# SCH_single_recovery_v1_copy_2022-11-08.net
KiCad netlist of a schematic drawn in EasyEDA
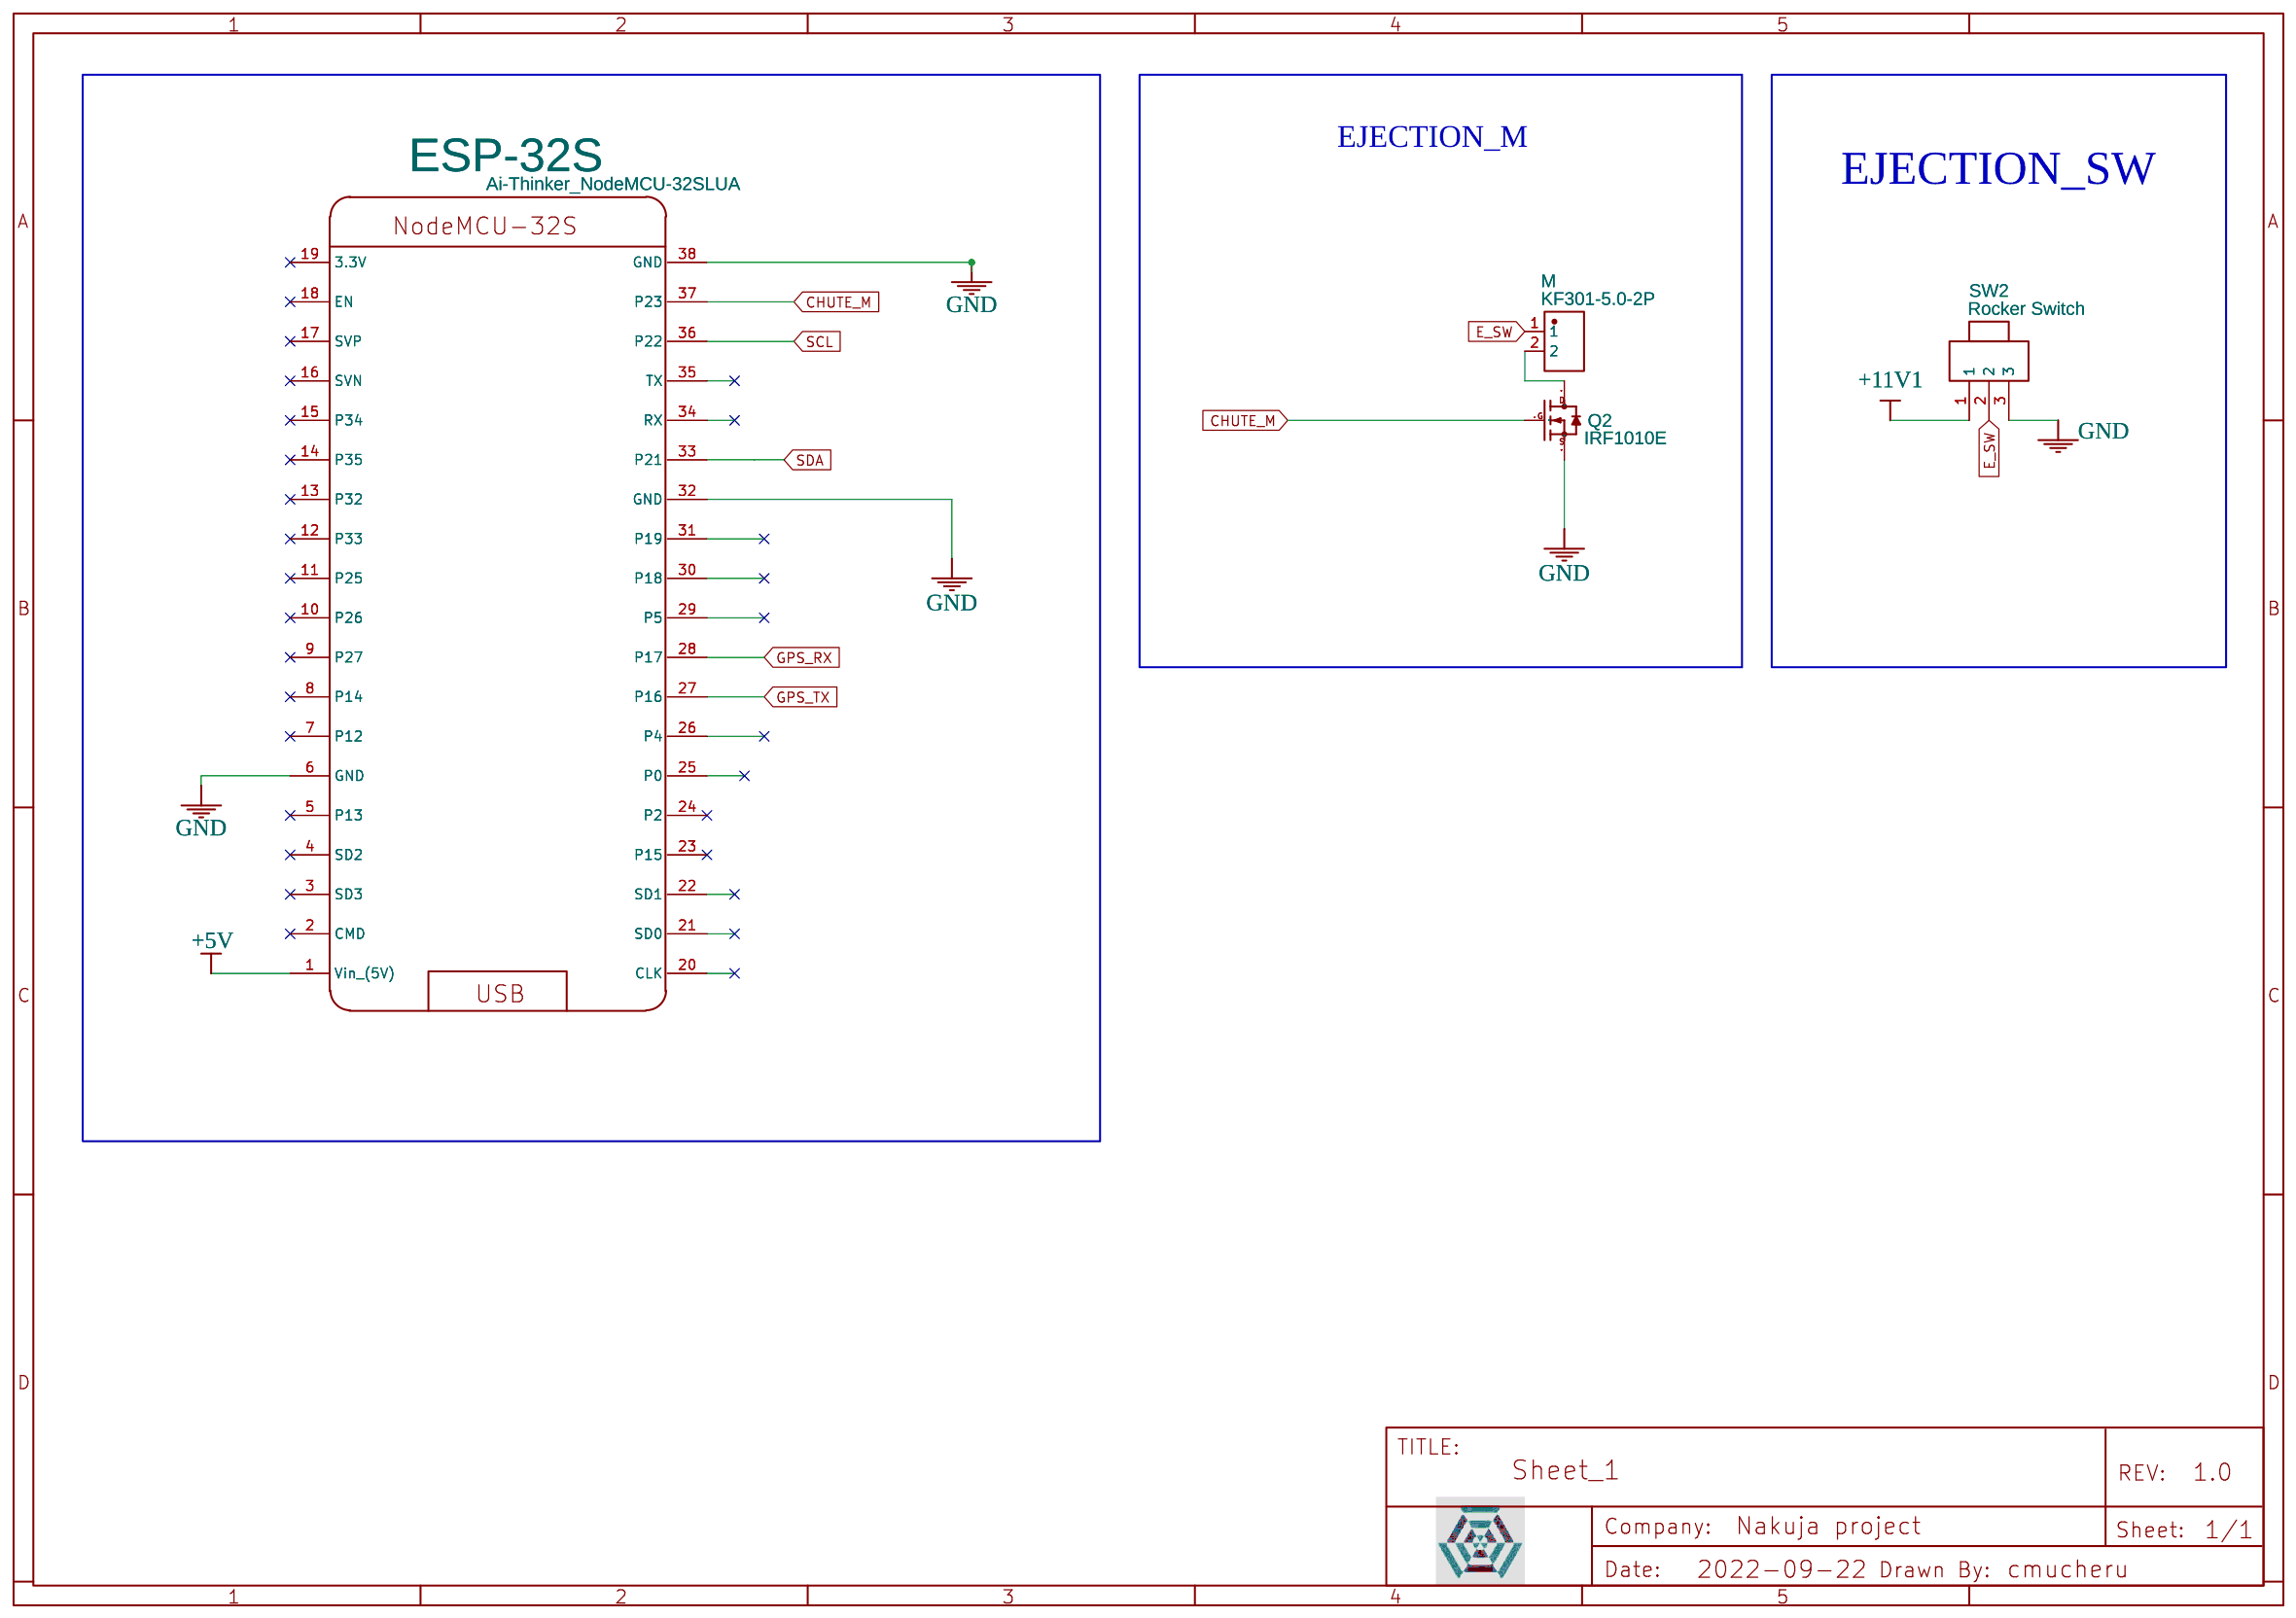
[diagram p0: Sheet_1 copy copy]
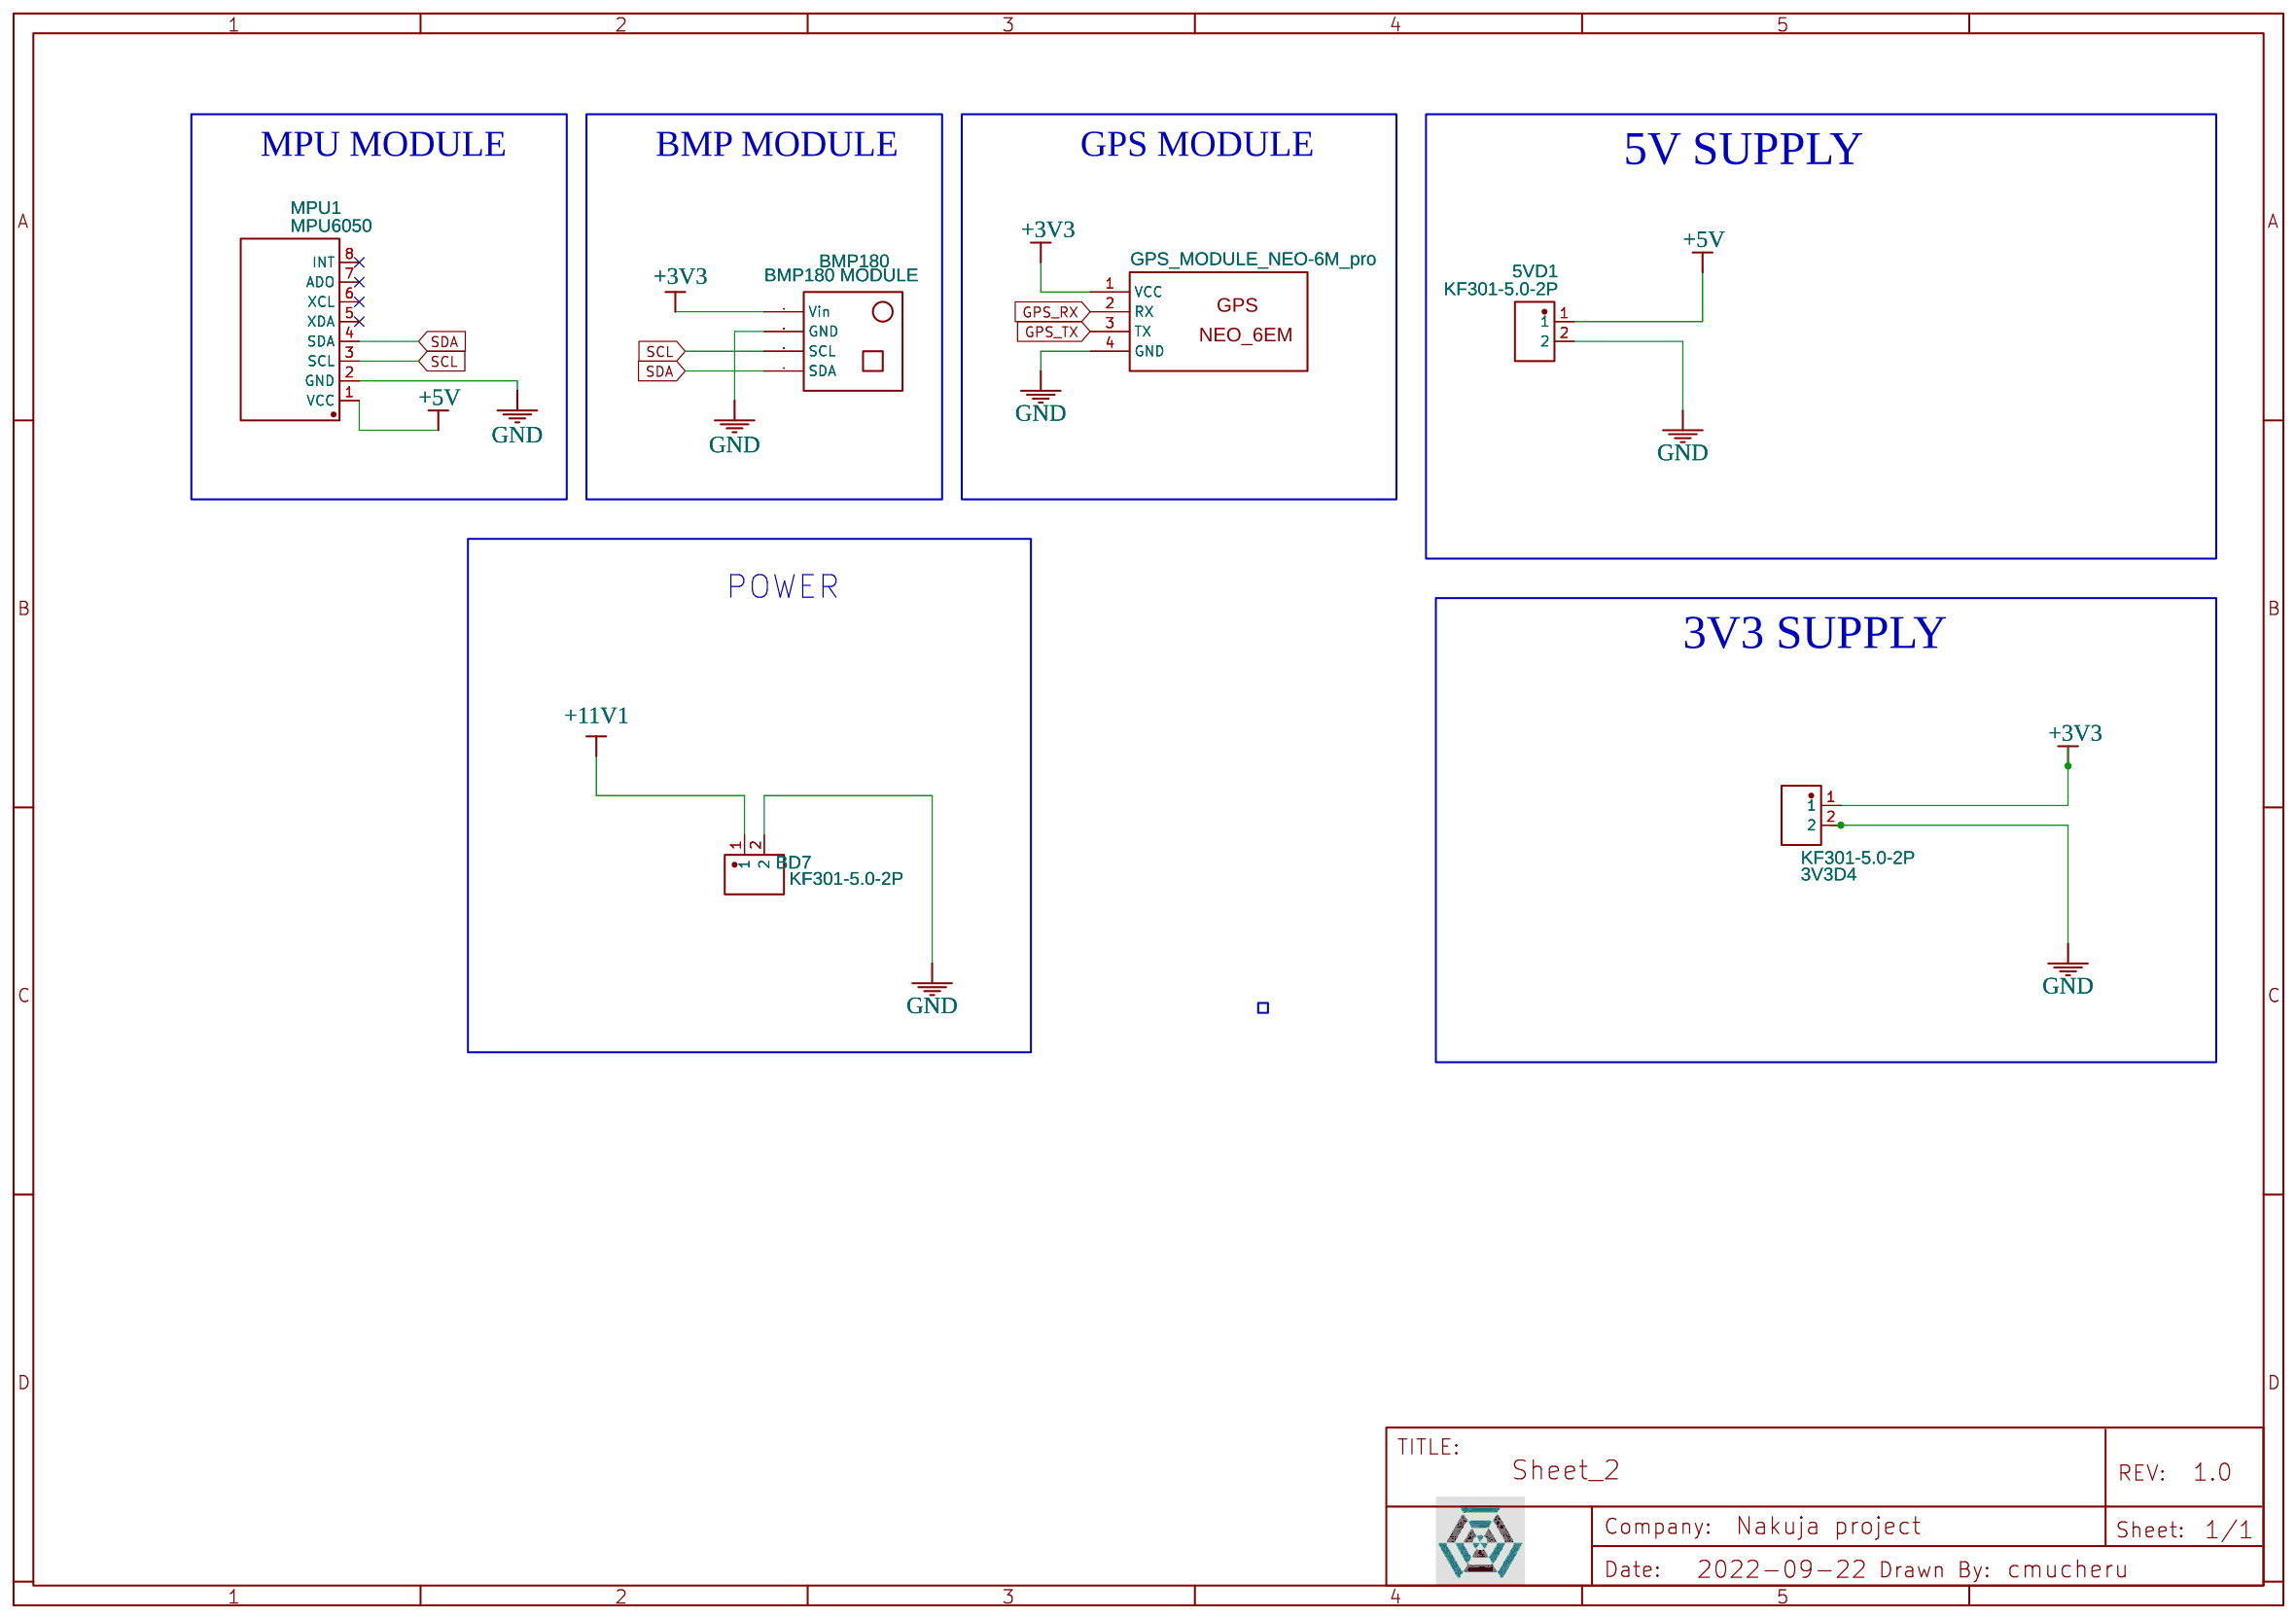
[diagram p1: Sheet_2 copy copy]

(export (version "E")
  (design (tool "Eeschema 10.0.6"))
  (components
    (comp (ref "ESP-32S")
      (value "Ai-Thinker_NodeMCU-32SLUA")
      (fields
        (field (name "BOM_Manufacturer Part") "NodeMCU-32SLua")
        (field (name "BOM_Supplier Part") "C111436")
      )
      (libsource (lib "") (part "Ai-Thinker_NodeMCU-32SLUA"))
    )
    (comp (ref "M")
      (value "KF301-5.0-2P")
      (fields (field (name "BOM_Supplier Part") "C474881"))
      (libsource (lib "") (part "KF301-5.0-2P"))
    )
    (comp (ref "Q2") (value "IRF1010E") (libsource (lib "") (part "Mosfet-N")))
    (comp (ref "SW2") (value "Rocker Switch") (libsource (lib "") (part "Rocker Switch")))
    (comp (ref "3V3D4")
      (value "KF301-5.0-2P")
      (fields (field (name "BOM_Supplier Part") "C474881"))
      (libsource (lib "") (part "KF301-5.0-2P_2"))
    )
    (comp (ref "5VD1")
      (value "KF301-5.0-2P")
      (fields (field (name "BOM_Supplier Part") "C474881"))
      (libsource (lib "") (part "KF301-5.0-2P_1"))
    )
    (comp (ref "BD7")
      (value "KF301-5.0-2P")
      (fields (field (name "BOM_Supplier Part") "C474881"))
      (libsource (lib "") (part "KF301-5.0-2P"))
    )
    (comp (ref "BMP180")
      (value "BMP180 MODULE")
      (fields (field (name "BOM_Manufacturer Part") "BMP180 (HW-596)"))
      (libsource (lib "") (part "BMP180 MODULE"))
    )
    (comp (ref "GPS_NEO-2EM")
      (value "GPS_MODULE_NEO-6M_pro")
      (libsource (lib "") (part "GPS_MODULE_NEO-6M_pro"))
    )
    (comp (ref "MPU1")
      (value "MPU6050")
      (fields (field (name "BOM_Supplier Part") "GY521"))
      (libsource (lib "") (part "MPU6050"))
    )
  )
  (nets
    (net (code "1") (name "+3V3") (class "Default")
      (node (ref "3V3D4") (pin "1") (pinfunction "1_1") (pintype "unspecified"))
      (node (ref "BMP180") (pin "1") (pinfunction "Vin_1") (pintype "unspecified"))
      (node (ref "GPS_NEO-2EM") (pin "1") (pinfunction "VCC_1") (pintype "passive"))
    )
    (net (code "2") (name "+5V") (class "Default")
      (node (ref "5VD1") (pin "1") (pinfunction "1_1") (pintype "unspecified"))
      (node (ref "ESP-32S") (pin "1") (pinfunction "Vin_(5V)_1") (pintype "unspecified"))
      (node (ref "MPU1") (pin "1") (pinfunction "VCC_1") (pintype "unspecified"))
    )
    (net (code "3") (name "+11V1") (class "Default")
      (node (ref "BD7") (pin "1") (pinfunction "1_1") (pintype "unspecified"))
      (node (ref "SW2") (pin "1") (pinfunction "1_1") (pintype "unspecified"))
    )
    (net (code "4") (name "CHUTE_M") (class "Default")
      (node (ref "ESP-32S") (pin "37") (pinfunction "P23_37") (pintype "unspecified"))
      (node (ref "Q2") (pin "1") (pinfunction "G_1") (pintype "unspecified"))
    )
    (net (code "5") (name "E_SW") (class "Default")
      (node (ref "M") (pin "1") (pinfunction "1_1") (pintype "unspecified"))
      (node (ref "SW2") (pin "2") (pinfunction "2_2") (pintype "unspecified"))
    )
    (net (code "6") (name "GND") (class "Default")
      (node (ref "3V3D4") (pin "2") (pinfunction "2_2") (pintype "unspecified"))
      (node (ref "5VD1") (pin "2") (pinfunction "2_2") (pintype "unspecified"))
      (node (ref "BD7") (pin "2") (pinfunction "2_2") (pintype "unspecified"))
      (node (ref "BMP180") (pin "2") (pinfunction "GND_2") (pintype "unspecified"))
      (node (ref "ESP-32S") (pin "32") (pinfunction "GND_32") (pintype "unspecified"))
      (node (ref "ESP-32S") (pin "38") (pinfunction "GND_38") (pintype "unspecified"))
      (node (ref "ESP-32S") (pin "6") (pinfunction "GND_6") (pintype "unspecified"))
      (node (ref "GPS_NEO-2EM") (pin "4") (pinfunction "GND_4") (pintype "passive"))
      (node (ref "MPU1") (pin "2") (pinfunction "GND_2") (pintype "unspecified"))
      (node (ref "Q2") (pin "3") (pinfunction "S_3") (pintype "unspecified"))
      (node (ref "SW2") (pin "3") (pinfunction "3_3") (pintype "unspecified"))
    )
    (net (code "7") (name "GPS_RX") (class "Default")
      (node (ref "ESP-32S") (pin "28") (pinfunction "P17_28") (pintype "unspecified"))
      (node (ref "GPS_NEO-2EM") (pin "2") (pinfunction "RX_2") (pintype "input"))
    )
    (net (code "8") (name "GPS_TX") (class "Default")
      (node (ref "ESP-32S") (pin "27") (pinfunction "P16_27") (pintype "unspecified"))
      (node (ref "GPS_NEO-2EM") (pin "3") (pinfunction "TX_3") (pintype "output"))
    )
    (net (code "9") (name "Net-(Q2-D)") (class "Default")
      (node (ref "M") (pin "2") (pinfunction "2_2") (pintype "unspecified"))
      (node (ref "Q2") (pin "2") (pinfunction "D_2") (pintype "unspecified"))
    )
    (net (code "10") (name "SCL") (class "Default")
      (node (ref "BMP180") (pin "3") (pinfunction "SCL_3") (pintype "unspecified"))
      (node (ref "ESP-32S") (pin "36") (pinfunction "P22_36") (pintype "unspecified"))
      (node (ref "MPU1") (pin "3") (pinfunction "SCL_3") (pintype "unspecified"))
    )
    (net (code "11") (name "SDA") (class "Default")
      (node (ref "BMP180") (pin "4") (pinfunction "SDA_4") (pintype "unspecified"))
      (node (ref "ESP-32S") (pin "33") (pinfunction "P21_33") (pintype "unspecified"))
      (node (ref "MPU1") (pin "4") (pinfunction "SDA_4") (pintype "unspecified"))
    )
    (net (code "12") (name "unconnected-(ESP-32S-3.3V-Pad19)") (class "Default")
      (node (ref "ESP-32S") (pin "19") (pinfunction "3.3V_19") (pintype "unspecified+no_connect"))
    )
    (net (code "13") (name "unconnected-(ESP-32S-CLK-Pad20)") (class "Default")
      (node (ref "ESP-32S") (pin "20") (pinfunction "CLK_20") (pintype "unspecified+no_connect"))
    )
    (net (code "14") (name "unconnected-(ESP-32S-CMD-Pad2)") (class "Default")
      (node (ref "ESP-32S") (pin "2") (pinfunction "CMD_2") (pintype "unspecified+no_connect"))
    )
    (net (code "15") (name "unconnected-(ESP-32S-EN-Pad18)") (class "Default")
      (node (ref "ESP-32S") (pin "18") (pinfunction "EN_18") (pintype "unspecified+no_connect"))
    )
    (net (code "16") (name "unconnected-(ESP-32S-P0-Pad25)") (class "Default")
      (node (ref "ESP-32S") (pin "25") (pinfunction "P0_25") (pintype "unspecified+no_connect"))
    )
    (net (code "17") (name "unconnected-(ESP-32S-P2-Pad24)") (class "Default")
      (node (ref "ESP-32S") (pin "24") (pinfunction "P2_24") (pintype "unspecified+no_connect"))
    )
    (net (code "18") (name "unconnected-(ESP-32S-P4-Pad26)") (class "Default")
      (node (ref "ESP-32S") (pin "26") (pinfunction "P4_26") (pintype "unspecified+no_connect"))
    )
    (net (code "19") (name "unconnected-(ESP-32S-P5-Pad29)") (class "Default")
      (node (ref "ESP-32S") (pin "29") (pinfunction "P5_29") (pintype "unspecified+no_connect"))
    )
    (net (code "20") (name "unconnected-(ESP-32S-P12-Pad7)") (class "Default")
      (node (ref "ESP-32S") (pin "7") (pinfunction "P12_7") (pintype "unspecified+no_connect"))
    )
    (net (code "21") (name "unconnected-(ESP-32S-P13-Pad5)") (class "Default")
      (node (ref "ESP-32S") (pin "5") (pinfunction "P13_5") (pintype "unspecified+no_connect"))
    )
    (net (code "22") (name "unconnected-(ESP-32S-P14-Pad8)") (class "Default")
      (node (ref "ESP-32S") (pin "8") (pinfunction "P14_8") (pintype "unspecified+no_connect"))
    )
    (net (code "23") (name "unconnected-(ESP-32S-P15-Pad23)") (class "Default")
      (node (ref "ESP-32S") (pin "23") (pinfunction "P15_23") (pintype "unspecified+no_connect"))
    )
    (net (code "24") (name "unconnected-(ESP-32S-P18-Pad30)") (class "Default")
      (node (ref "ESP-32S") (pin "30") (pinfunction "P18_30") (pintype "unspecified+no_connect"))
    )
    (net (code "25") (name "unconnected-(ESP-32S-P19-Pad31)") (class "Default")
      (node (ref "ESP-32S") (pin "31") (pinfunction "P19_31") (pintype "unspecified+no_connect"))
    )
    (net (code "26") (name "unconnected-(ESP-32S-P25-Pad11)") (class "Default")
      (node (ref "ESP-32S") (pin "11") (pinfunction "P25_11") (pintype "unspecified+no_connect"))
    )
    (net (code "27") (name "unconnected-(ESP-32S-P26-Pad10)") (class "Default")
      (node (ref "ESP-32S") (pin "10") (pinfunction "P26_10") (pintype "unspecified+no_connect"))
    )
    (net (code "28") (name "unconnected-(ESP-32S-P27-Pad9)") (class "Default")
      (node (ref "ESP-32S") (pin "9") (pinfunction "P27_9") (pintype "unspecified+no_connect"))
    )
    (net (code "29") (name "unconnected-(ESP-32S-P32-Pad13)") (class "Default")
      (node (ref "ESP-32S") (pin "13") (pinfunction "P32_13") (pintype "unspecified+no_connect"))
    )
    (net (code "30") (name "unconnected-(ESP-32S-P33-Pad12)") (class "Default")
      (node (ref "ESP-32S") (pin "12") (pinfunction "P33_12") (pintype "unspecified+no_connect"))
    )
    (net (code "31") (name "unconnected-(ESP-32S-P34-Pad15)") (class "Default")
      (node (ref "ESP-32S") (pin "15") (pinfunction "P34_15") (pintype "unspecified+no_connect"))
    )
    (net (code "32") (name "unconnected-(ESP-32S-P35-Pad14)") (class "Default")
      (node (ref "ESP-32S") (pin "14") (pinfunction "P35_14") (pintype "unspecified+no_connect"))
    )
    (net (code "33") (name "unconnected-(ESP-32S-RX-Pad34)") (class "Default")
      (node (ref "ESP-32S") (pin "34") (pinfunction "RX_34") (pintype "unspecified+no_connect"))
    )
    (net (code "34") (name "unconnected-(ESP-32S-SD0-Pad21)") (class "Default")
      (node (ref "ESP-32S") (pin "21") (pinfunction "SD0_21") (pintype "unspecified+no_connect"))
    )
    (net (code "35") (name "unconnected-(ESP-32S-SD1-Pad22)") (class "Default")
      (node (ref "ESP-32S") (pin "22") (pinfunction "SD1_22") (pintype "unspecified+no_connect"))
    )
    (net (code "36") (name "unconnected-(ESP-32S-SD2-Pad4)") (class "Default")
      (node (ref "ESP-32S") (pin "4") (pinfunction "SD2_4") (pintype "unspecified+no_connect"))
    )
    (net (code "37") (name "unconnected-(ESP-32S-SD3-Pad3)") (class "Default")
      (node (ref "ESP-32S") (pin "3") (pinfunction "SD3_3") (pintype "unspecified+no_connect"))
    )
    (net (code "38") (name "unconnected-(ESP-32S-SVN-Pad16)") (class "Default")
      (node (ref "ESP-32S") (pin "16") (pinfunction "SVN_16") (pintype "unspecified+no_connect"))
    )
    (net (code "39") (name "unconnected-(ESP-32S-SVP-Pad17)") (class "Default")
      (node (ref "ESP-32S") (pin "17") (pinfunction "SVP_17") (pintype "unspecified+no_connect"))
    )
    (net (code "40") (name "unconnected-(ESP-32S-TX-Pad35)") (class "Default")
      (node (ref "ESP-32S") (pin "35") (pinfunction "TX_35") (pintype "unspecified+no_connect"))
    )
    (net (code "41") (name "unconnected-(MPU1-ADO-Pad7)") (class "Default")
      (node (ref "MPU1") (pin "7") (pinfunction "ADO_7") (pintype "unspecified+no_connect"))
    )
    (net (code "42") (name "unconnected-(MPU1-INT-Pad8)") (class "Default")
      (node (ref "MPU1") (pin "8") (pinfunction "INT_8") (pintype "unspecified+no_connect"))
    )
    (net (code "43") (name "unconnected-(MPU1-XCL-Pad6)") (class "Default")
      (node (ref "MPU1") (pin "6") (pinfunction "XCL_6") (pintype "unspecified+no_connect"))
    )
    (net (code "44") (name "unconnected-(MPU1-XDA-Pad5)") (class "Default")
      (node (ref "MPU1") (pin "5") (pinfunction "XDA_5") (pintype "unspecified+no_connect"))
    )
  )
)
